# indication.net
KiCad netlist of a schematic drawn in Altium Designer
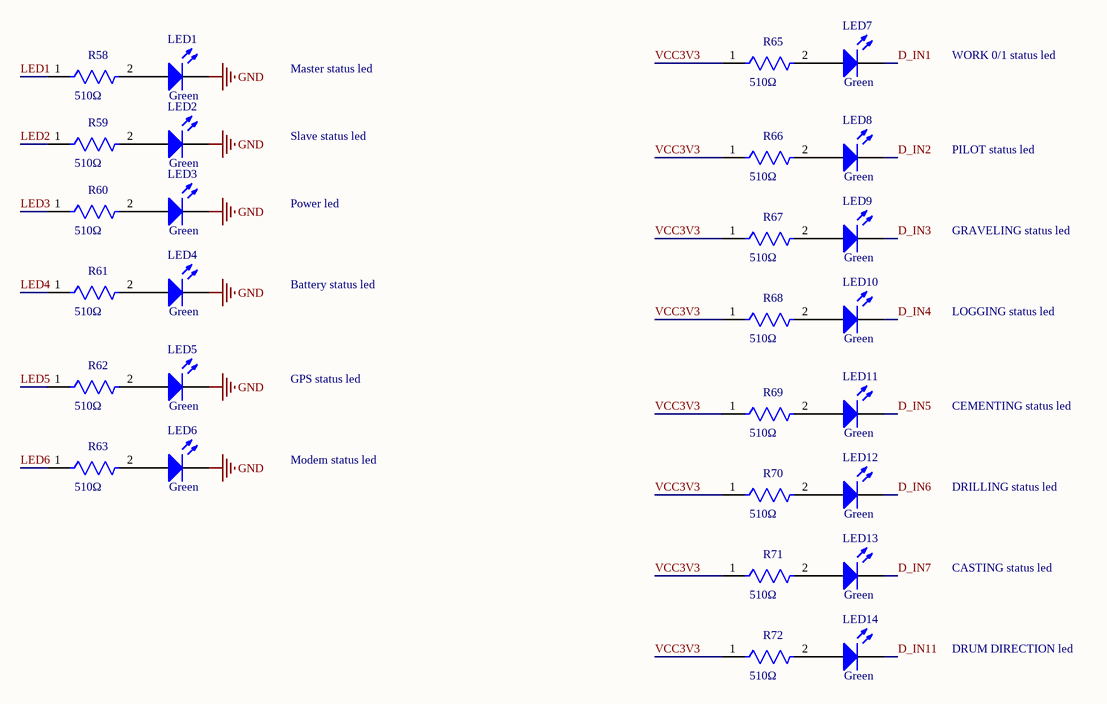
[diagram p0: indication.SchDoc]

(export (version "E")
  (design (tool "Eeschema 10.0.6"))
  (components
    (comp (ref "LED1")
      (value "150080GS75000")
      (footprint "0805_A")
      (description "SMD mono-color Chip LED, WL-SMCW, Green")
      (fields (field (name "COLOR") "Green") (field (name "MANUFACTURER") "Wuerth Elektronik"))
      (libsource (lib "Altium Content Vault") (part "WE-LED_K1A2-2"))
    )
    (comp (ref "LED2")
      (value "150080GS75000")
      (footprint "0805_A")
      (description "SMD mono-color Chip LED, WL-SMCW, Green")
      (fields (field (name "COLOR") "Green") (field (name "MANUFACTURER") "Wuerth Elektronik"))
      (libsource (lib "Altium Content Vault") (part "WE-LED_K1A2-2"))
    )
    (comp (ref "LED3")
      (value "150080GS75000")
      (footprint "0805_A")
      (description "SMD mono-color Chip LED, WL-SMCW, Green")
      (fields (field (name "COLOR") "Green") (field (name "MANUFACTURER") "Wuerth Elektronik"))
      (libsource (lib "Altium Content Vault") (part "WE-LED_K1A2-2"))
    )
    (comp (ref "LED4")
      (value "150080GS75000")
      (footprint "0805_A")
      (description "SMD mono-color Chip LED, WL-SMCW, Green")
      (fields (field (name "COLOR") "Green") (field (name "MANUFACTURER") "Wuerth Elektronik"))
      (libsource (lib "Altium Content Vault") (part "WE-LED_K1A2-2"))
    )
    (comp (ref "LED5")
      (value "150080GS75000")
      (footprint "0805_A")
      (description "SMD mono-color Chip LED, WL-SMCW, Green")
      (fields (field (name "COLOR") "Green") (field (name "MANUFACTURER") "Wuerth Elektronik"))
      (libsource (lib "Altium Content Vault") (part "WE-LED_K1A2-2"))
    )
    (comp (ref "LED6")
      (value "150080GS75000")
      (footprint "0805_A")
      (description "SMD mono-color Chip LED, WL-SMCW, Green")
      (fields (field (name "COLOR") "Green") (field (name "MANUFACTURER") "Wuerth Elektronik"))
      (libsource (lib "Altium Content Vault") (part "WE-LED_K1A2-2"))
    )
    (comp (ref "LED7")
      (value "150080GS75000")
      (footprint "0805_A")
      (description "SMD mono-color Chip LED, WL-SMCW, Green")
      (fields (field (name "COLOR") "Green") (field (name "MANUFACTURER") "Wuerth Elektronik"))
      (libsource (lib "Altium Content Vault") (part "WE-LED_K1A2-2"))
    )
    (comp (ref "LED8")
      (value "150080GS75000")
      (footprint "0805_A")
      (description "SMD mono-color Chip LED, WL-SMCW, Green")
      (fields (field (name "COLOR") "Green") (field (name "MANUFACTURER") "Wuerth Elektronik"))
      (libsource (lib "Altium Content Vault") (part "WE-LED_K1A2-2"))
    )
    (comp (ref "LED9")
      (value "150080GS75000")
      (footprint "0805_A")
      (description "SMD mono-color Chip LED, WL-SMCW, Green")
      (fields (field (name "COLOR") "Green") (field (name "MANUFACTURER") "Wuerth Elektronik"))
      (libsource (lib "Altium Content Vault") (part "WE-LED_K1A2-2"))
    )
    (comp (ref "LED10")
      (value "150080GS75000")
      (footprint "0805_A")
      (description "SMD mono-color Chip LED, WL-SMCW, Green")
      (fields (field (name "COLOR") "Green") (field (name "MANUFACTURER") "Wuerth Elektronik"))
      (libsource (lib "Altium Content Vault") (part "WE-LED_K1A2-2"))
    )
    (comp (ref "LED11")
      (value "150080GS75000")
      (footprint "0805_A")
      (description "SMD mono-color Chip LED, WL-SMCW, Green")
      (fields (field (name "COLOR") "Green") (field (name "MANUFACTURER") "Wuerth Elektronik"))
      (libsource (lib "Altium Content Vault") (part "WE-LED_K1A2-2"))
    )
    (comp (ref "LED12")
      (value "150080GS75000")
      (footprint "0805_A")
      (description "SMD mono-color Chip LED, WL-SMCW, Green")
      (fields (field (name "COLOR") "Green") (field (name "MANUFACTURER") "Wuerth Elektronik"))
      (libsource (lib "Altium Content Vault") (part "WE-LED_K1A2-2"))
    )
    (comp (ref "LED13")
      (value "150080GS75000")
      (footprint "0805_A")
      (description "SMD mono-color Chip LED, WL-SMCW, Green")
      (fields (field (name "COLOR") "Green") (field (name "MANUFACTURER") "Wuerth Elektronik"))
      (libsource (lib "Altium Content Vault") (part "WE-LED_K1A2-2"))
    )
    (comp (ref "LED14")
      (value "150080GS75000")
      (footprint "0805_A")
      (description "SMD mono-color Chip LED, WL-SMCW, Green")
      (fields (field (name "COLOR") "Green") (field (name "MANUFACTURER") "Wuerth Elektronik"))
      (libsource (lib "Altium Content Vault") (part "WE-LED_K1A2-2"))
    )
    (comp (ref "R58")
      (value "AC0805FR-07510RL")
      (footprint "FP-AC0805-MFG")
      (description "RES SMD 510 OHM 1% 1/8W 0805")
      (fields
        (field (name "TOLERANCE") "0.01")
        (field (name "MANUFACTURER") "Yageo")
        (field (name "RESISTANCE") "510Ω")
      )
      (libsource (lib "Altium Content Vault") (part "1029c3af85768c4190bb7ad29bc67b5"))
    )
    (comp (ref "R59")
      (value "AC0805FR-07510RL")
      (footprint "FP-AC0805-MFG")
      (description "RES SMD 510 OHM 1% 1/8W 0805")
      (fields
        (field (name "TOLERANCE") "0.01")
        (field (name "MANUFACTURER") "Yageo")
        (field (name "RESISTANCE") "510Ω")
      )
      (libsource (lib "Altium Content Vault") (part "1029c3af85768c4190bb7ad29bc67b5"))
    )
    (comp (ref "R60")
      (value "AC0805FR-07510RL")
      (footprint "FP-AC0805-MFG")
      (description "RES SMD 510 OHM 1% 1/8W 0805")
      (fields
        (field (name "TOLERANCE") "0.01")
        (field (name "MANUFACTURER") "Yageo")
        (field (name "RESISTANCE") "510Ω")
      )
      (libsource (lib "Altium Content Vault") (part "1029c3af85768c4190bb7ad29bc67b5"))
    )
    (comp (ref "R61")
      (value "AC0805FR-07510RL")
      (footprint "FP-AC0805-MFG")
      (description "RES SMD 510 OHM 1% 1/8W 0805")
      (fields
        (field (name "TOLERANCE") "0.01")
        (field (name "MANUFACTURER") "Yageo")
        (field (name "RESISTANCE") "510Ω")
      )
      (libsource (lib "Altium Content Vault") (part "1029c3af85768c4190bb7ad29bc67b5"))
    )
    (comp (ref "R62")
      (value "AC0805FR-07510RL")
      (footprint "FP-AC0805-MFG")
      (description "RES SMD 510 OHM 1% 1/8W 0805")
      (fields
        (field (name "TOLERANCE") "0.01")
        (field (name "MANUFACTURER") "Yageo")
        (field (name "RESISTANCE") "510Ω")
      )
      (libsource (lib "Altium Content Vault") (part "1029c3af85768c4190bb7ad29bc67b5"))
    )
    (comp (ref "R63")
      (value "AC0805FR-07510RL")
      (footprint "FP-AC0805-MFG")
      (description "RES SMD 510 OHM 1% 1/8W 0805")
      (fields
        (field (name "TOLERANCE") "0.01")
        (field (name "MANUFACTURER") "Yageo")
        (field (name "RESISTANCE") "510Ω")
      )
      (libsource (lib "Altium Content Vault") (part "1029c3af85768c4190bb7ad29bc67b5"))
    )
    (comp (ref "R65")
      (value "AC0805FR-07510RL")
      (footprint "FP-AC0805-MFG")
      (description "RES SMD 510 OHM 1% 1/8W 0805")
      (fields
        (field (name "TOLERANCE") "0.01")
        (field (name "MANUFACTURER") "Yageo")
        (field (name "RESISTANCE") "510Ω")
      )
      (libsource (lib "Altium Content Vault") (part "1029c3af85768c4190bb7ad29bc67b5"))
    )
    (comp (ref "R66")
      (value "AC0805FR-07510RL")
      (footprint "FP-AC0805-MFG")
      (description "RES SMD 510 OHM 1% 1/8W 0805")
      (fields
        (field (name "TOLERANCE") "0.01")
        (field (name "MANUFACTURER") "Yageo")
        (field (name "RESISTANCE") "510Ω")
      )
      (libsource (lib "Altium Content Vault") (part "1029c3af85768c4190bb7ad29bc67b5"))
    )
    (comp (ref "R67")
      (value "AC0805FR-07510RL")
      (footprint "FP-AC0805-MFG")
      (description "RES SMD 510 OHM 1% 1/8W 0805")
      (fields
        (field (name "TOLERANCE") "0.01")
        (field (name "MANUFACTURER") "Yageo")
        (field (name "RESISTANCE") "510Ω")
      )
      (libsource (lib "Altium Content Vault") (part "1029c3af85768c4190bb7ad29bc67b5"))
    )
    (comp (ref "R68")
      (value "AC0805FR-07510RL")
      (footprint "FP-AC0805-MFG")
      (description "RES SMD 510 OHM 1% 1/8W 0805")
      (fields
        (field (name "TOLERANCE") "0.01")
        (field (name "MANUFACTURER") "Yageo")
        (field (name "RESISTANCE") "510Ω")
      )
      (libsource (lib "Altium Content Vault") (part "1029c3af85768c4190bb7ad29bc67b5"))
    )
    (comp (ref "R69")
      (value "AC0805FR-07510RL")
      (footprint "FP-AC0805-MFG")
      (description "RES SMD 510 OHM 1% 1/8W 0805")
      (fields
        (field (name "TOLERANCE") "0.01")
        (field (name "MANUFACTURER") "Yageo")
        (field (name "RESISTANCE") "510Ω")
      )
      (libsource (lib "Altium Content Vault") (part "1029c3af85768c4190bb7ad29bc67b5"))
    )
    (comp (ref "R70")
      (value "AC0805FR-07510RL")
      (footprint "FP-AC0805-MFG")
      (description "RES SMD 510 OHM 1% 1/8W 0805")
      (fields
        (field (name "TOLERANCE") "0.01")
        (field (name "MANUFACTURER") "Yageo")
        (field (name "RESISTANCE") "510Ω")
      )
      (libsource (lib "Altium Content Vault") (part "1029c3af85768c4190bb7ad29bc67b5"))
    )
    (comp (ref "R71")
      (value "AC0805FR-07510RL")
      (footprint "FP-AC0805-MFG")
      (description "RES SMD 510 OHM 1% 1/8W 0805")
      (fields
        (field (name "TOLERANCE") "0.01")
        (field (name "MANUFACTURER") "Yageo")
        (field (name "RESISTANCE") "510Ω")
      )
      (libsource (lib "Altium Content Vault") (part "1029c3af85768c4190bb7ad29bc67b5"))
    )
    (comp (ref "R72")
      (value "AC0805FR-07510RL")
      (footprint "FP-AC0805-MFG")
      (description "RES SMD 510 OHM 1% 1/8W 0805")
      (fields
        (field (name "TOLERANCE") "0.01")
        (field (name "MANUFACTURER") "Yageo")
        (field (name "RESISTANCE") "510Ω")
      )
      (libsource (lib "Altium Content Vault") (part "1029c3af85768c4190bb7ad29bc67b5"))
    )
  )
  (nets
    (net (code "1") (name "/D_IN1") (class "Default")
      (node (ref "LED7") (pin "1") (pinfunction "K_1") (pintype "passive"))
    )
    (net (code "2") (name "/D_IN2") (class "Default")
      (node (ref "LED8") (pin "1") (pinfunction "K_1") (pintype "passive"))
    )
    (net (code "3") (name "/D_IN3") (class "Default")
      (node (ref "LED9") (pin "1") (pinfunction "K_1") (pintype "passive"))
    )
    (net (code "4") (name "/D_IN4") (class "Default")
      (node (ref "LED10") (pin "1") (pinfunction "K_1") (pintype "passive"))
    )
    (net (code "5") (name "/D_IN5") (class "Default")
      (node (ref "LED11") (pin "1") (pinfunction "K_1") (pintype "passive"))
    )
    (net (code "6") (name "/D_IN6") (class "Default")
      (node (ref "LED12") (pin "1") (pinfunction "K_1") (pintype "passive"))
    )
    (net (code "7") (name "/D_IN7") (class "Default")
      (node (ref "LED13") (pin "1") (pinfunction "K_1") (pintype "passive"))
    )
    (net (code "8") (name "/D_IN11") (class "Default")
      (node (ref "LED14") (pin "1") (pinfunction "K_1") (pintype "passive"))
    )
    (net (code "9") (name "/LED1") (class "Default")
      (node (ref "R58") (pin "1") (pinfunction "1_1") (pintype "passive"))
    )
    (net (code "10") (name "/LED2") (class "Default")
      (node (ref "R59") (pin "1") (pinfunction "1_1") (pintype "passive"))
    )
    (net (code "11") (name "/LED3") (class "Default")
      (node (ref "R60") (pin "1") (pinfunction "1_1") (pintype "passive"))
    )
    (net (code "12") (name "/LED4") (class "Default")
      (node (ref "R61") (pin "1") (pinfunction "1_1") (pintype "passive"))
    )
    (net (code "13") (name "/LED5") (class "Default")
      (node (ref "R62") (pin "1") (pinfunction "1_1") (pintype "passive"))
    )
    (net (code "14") (name "/LED6") (class "Default")
      (node (ref "R63") (pin "1") (pinfunction "1_1") (pintype "passive"))
    )
    (net (code "15") (name "/VCC3V3") (class "Default")
      (node (ref "R65") (pin "1") (pinfunction "1_1") (pintype "passive"))
      (node (ref "R66") (pin "1") (pinfunction "1_1") (pintype "passive"))
      (node (ref "R67") (pin "1") (pinfunction "1_1") (pintype "passive"))
      (node (ref "R68") (pin "1") (pinfunction "1_1") (pintype "passive"))
      (node (ref "R69") (pin "1") (pinfunction "1_1") (pintype "passive"))
      (node (ref "R70") (pin "1") (pinfunction "1_1") (pintype "passive"))
      (node (ref "R71") (pin "1") (pinfunction "1_1") (pintype "passive"))
      (node (ref "R72") (pin "1") (pinfunction "1_1") (pintype "passive"))
    )
    (net (code "16") (name "GND") (class "Default")
      (node (ref "LED1") (pin "1") (pinfunction "K_1") (pintype "passive"))
      (node (ref "LED2") (pin "1") (pinfunction "K_1") (pintype "passive"))
      (node (ref "LED3") (pin "1") (pinfunction "K_1") (pintype "passive"))
      (node (ref "LED4") (pin "1") (pinfunction "K_1") (pintype "passive"))
      (node (ref "LED5") (pin "1") (pinfunction "K_1") (pintype "passive"))
      (node (ref "LED6") (pin "1") (pinfunction "K_1") (pintype "passive"))
    )
    (net (code "17") (name "Net-(LED1-A)") (class "Default")
      (node (ref "LED1") (pin "2") (pinfunction "A_2") (pintype "passive"))
      (node (ref "R58") (pin "2") (pinfunction "2_2") (pintype "passive"))
    )
    (net (code "18") (name "Net-(LED2-A)") (class "Default")
      (node (ref "LED2") (pin "2") (pinfunction "A_2") (pintype "passive"))
      (node (ref "R59") (pin "2") (pinfunction "2_2") (pintype "passive"))
    )
    (net (code "19") (name "Net-(LED3-A)") (class "Default")
      (node (ref "LED3") (pin "2") (pinfunction "A_2") (pintype "passive"))
      (node (ref "R60") (pin "2") (pinfunction "2_2") (pintype "passive"))
    )
    (net (code "20") (name "Net-(LED4-A)") (class "Default")
      (node (ref "LED4") (pin "2") (pinfunction "A_2") (pintype "passive"))
      (node (ref "R61") (pin "2") (pinfunction "2_2") (pintype "passive"))
    )
    (net (code "21") (name "Net-(LED5-A)") (class "Default")
      (node (ref "LED5") (pin "2") (pinfunction "A_2") (pintype "passive"))
      (node (ref "R62") (pin "2") (pinfunction "2_2") (pintype "passive"))
    )
    (net (code "22") (name "Net-(LED6-A)") (class "Default")
      (node (ref "LED6") (pin "2") (pinfunction "A_2") (pintype "passive"))
      (node (ref "R63") (pin "2") (pinfunction "2_2") (pintype "passive"))
    )
    (net (code "23") (name "Net-(LED7-A)") (class "Default")
      (node (ref "LED7") (pin "2") (pinfunction "A_2") (pintype "passive"))
      (node (ref "R65") (pin "2") (pinfunction "2_2") (pintype "passive"))
    )
    (net (code "24") (name "Net-(LED8-A)") (class "Default")
      (node (ref "LED8") (pin "2") (pinfunction "A_2") (pintype "passive"))
      (node (ref "R66") (pin "2") (pinfunction "2_2") (pintype "passive"))
    )
    (net (code "25") (name "Net-(LED9-A)") (class "Default")
      (node (ref "LED9") (pin "2") (pinfunction "A_2") (pintype "passive"))
      (node (ref "R67") (pin "2") (pinfunction "2_2") (pintype "passive"))
    )
    (net (code "26") (name "Net-(LED10-A)") (class "Default")
      (node (ref "LED10") (pin "2") (pinfunction "A_2") (pintype "passive"))
      (node (ref "R68") (pin "2") (pinfunction "2_2") (pintype "passive"))
    )
    (net (code "27") (name "Net-(LED11-A)") (class "Default")
      (node (ref "LED11") (pin "2") (pinfunction "A_2") (pintype "passive"))
      (node (ref "R69") (pin "2") (pinfunction "2_2") (pintype "passive"))
    )
    (net (code "28") (name "Net-(LED12-A)") (class "Default")
      (node (ref "LED12") (pin "2") (pinfunction "A_2") (pintype "passive"))
      (node (ref "R70") (pin "2") (pinfunction "2_2") (pintype "passive"))
    )
    (net (code "29") (name "Net-(LED13-A)") (class "Default")
      (node (ref "LED13") (pin "2") (pinfunction "A_2") (pintype "passive"))
      (node (ref "R71") (pin "2") (pinfunction "2_2") (pintype "passive"))
    )
    (net (code "30") (name "Net-(LED14-A)") (class "Default")
      (node (ref "LED14") (pin "2") (pinfunction "A_2") (pintype "passive"))
      (node (ref "R72") (pin "2") (pinfunction "2_2") (pintype "passive"))
    )
  )
)
